# dcdc3to5.net
KiCad netlist of a schematic drawn in EAGLE
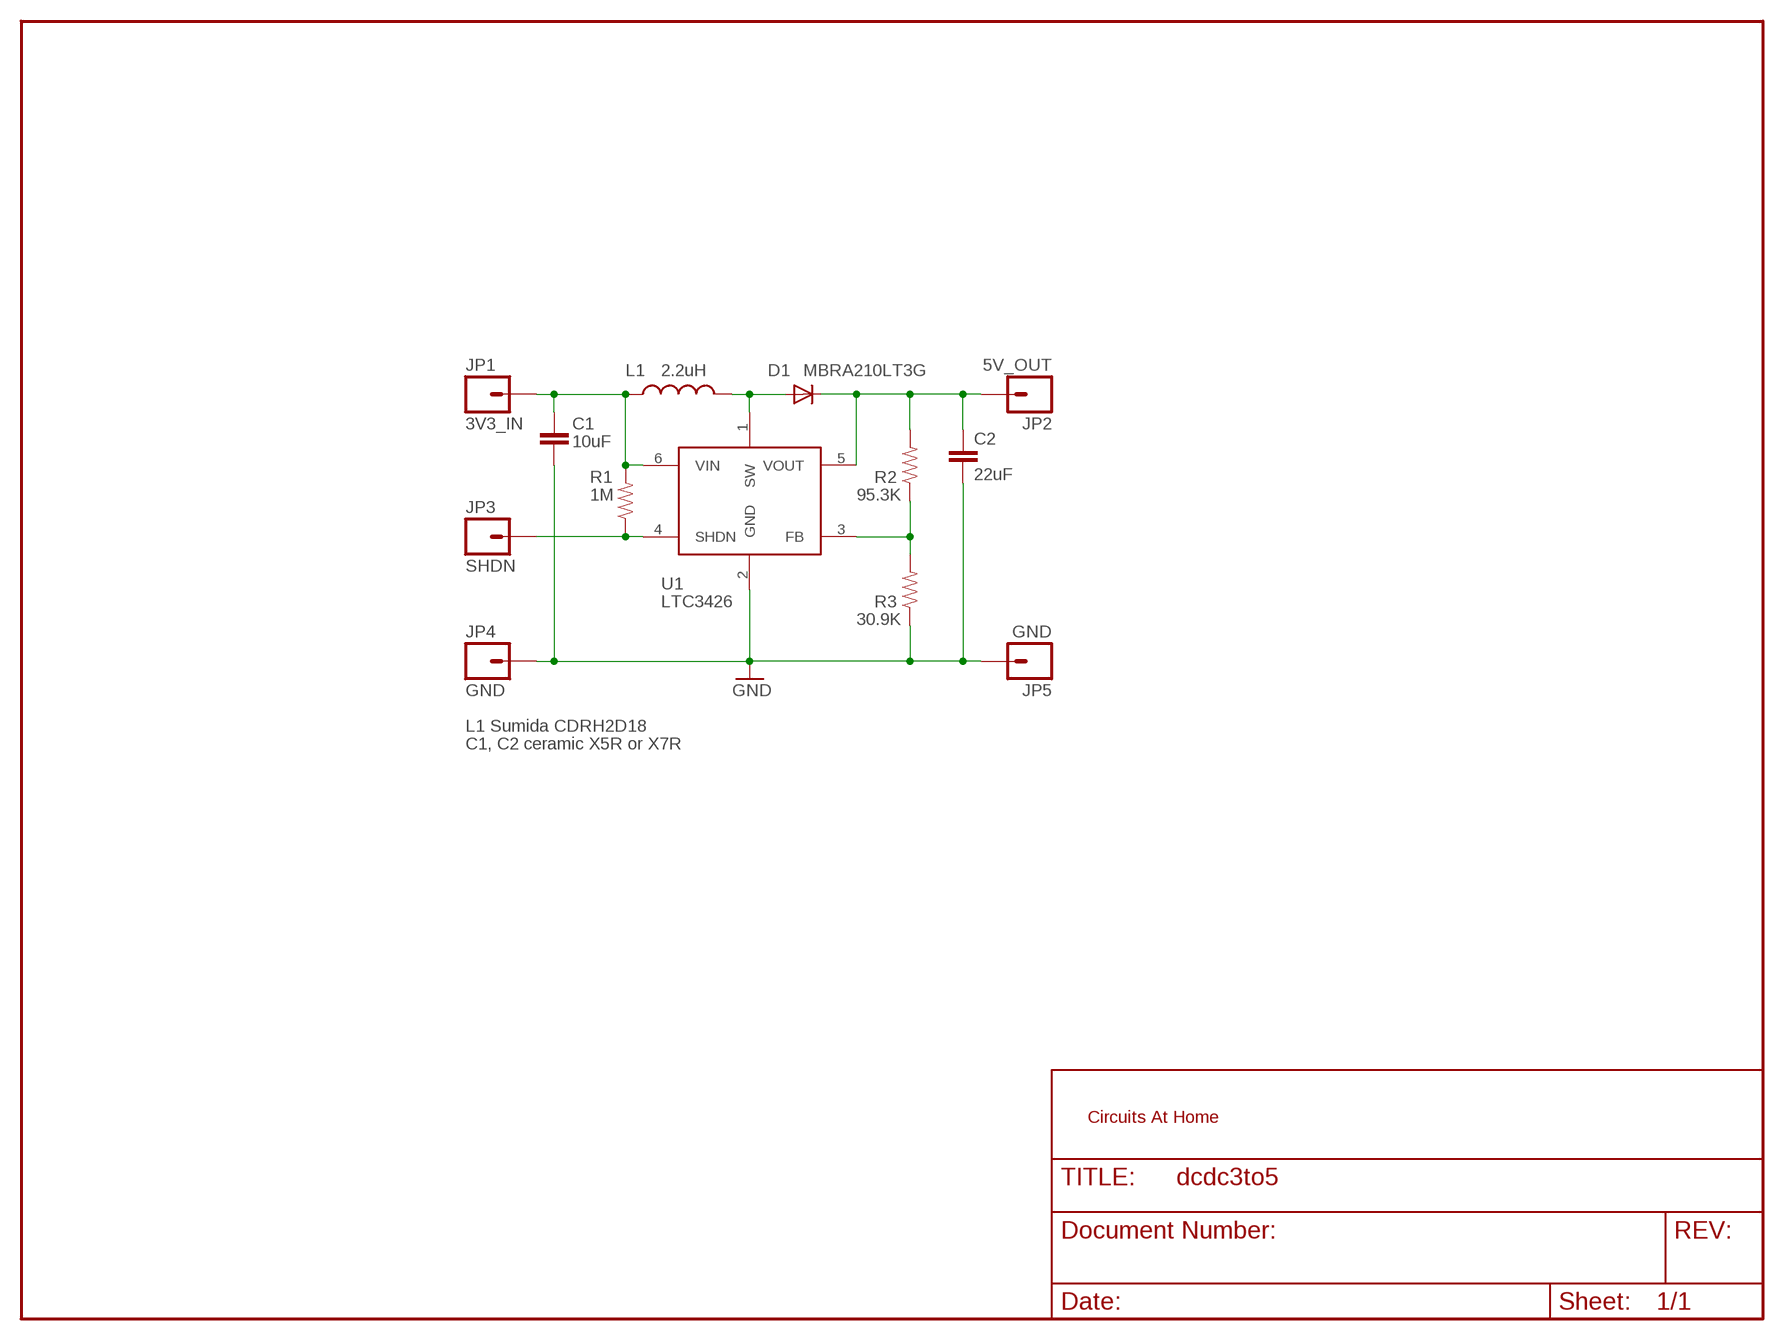
[diagram p0: schematic, sheet 1]

(export (version "E")
  (design (tool "Eeschema 10.0.6"))
  (components
    (comp (ref "C1")
      (value "10uF")
      (footprint "eagle-import:0603")
      (libsource (lib "eagle-import") (part "CAP0603"))
    )
    (comp (ref "C2")
      (value "22uF")
      (footprint "eagle-import:1206")
      (libsource (lib "eagle-import") (part "CAP1206"))
    )
    (comp (ref "D1")
      (value "MBRA210LT3G")
      (footprint "eagle-import:SMA-DIODE")
      (libsource (lib "eagle-import") (part "DIODESMA"))
    )
    (comp (ref "JP1")
      (value "3V3_IN")
      (footprint "eagle-import:1X01")
      (libsource (lib "eagle-import") (part "M01PTH"))
    )
    (comp (ref "JP2")
      (value "5V_OUT")
      (footprint "eagle-import:1X01")
      (libsource (lib "eagle-import") (part "M01PTH"))
    )
    (comp (ref "JP3")
      (value "SHDN")
      (footprint "eagle-import:1X01")
      (libsource (lib "eagle-import") (part "M01PTH"))
    )
    (comp (ref "JP4")
      (value "GND")
      (footprint "eagle-import:1X01")
      (libsource (lib "eagle-import") (part "M01PTH"))
    )
    (comp (ref "JP5")
      (value "GND")
      (footprint "eagle-import:1X01")
      (libsource (lib "eagle-import") (part "M01PTH"))
    )
    (comp (ref "L1")
      (value "2.2uH")
      (footprint "eagle-import:1_3X1_3")
      (libsource (lib "eagle-import") (part "INDUCTOR1313"))
    )
    (comp (ref "R1")
      (value "1M")
      (footprint "eagle-import:0603")
      (libsource (lib "eagle-import") (part "RESISTOR0603"))
    )
    (comp (ref "R2")
      (value "95.3K")
      (footprint "eagle-import:0603")
      (libsource (lib "eagle-import") (part "RESISTOR0603"))
    )
    (comp (ref "R3")
      (value "30.9K")
      (footprint "eagle-import:0603")
      (libsource (lib "eagle-import") (part "RESISTOR0603"))
    )
    (comp (ref "U1")
      (value "LTC3426")
      (footprint "eagle-import:SOT23-6")
      (libsource (lib "eagle-import") (part "LTC3426"))
    )
  )
  (nets
    (net (code "1") (name "GND") (class "Default")
      (node (ref "C1") (pin "2") (pinfunction "2_2") (pintype "passive"))
      (node (ref "C2") (pin "2") (pinfunction "2_2") (pintype "passive"))
      (node (ref "JP4") (pin "1") (pinfunction "1_1") (pintype "passive"))
      (node (ref "JP5") (pin "1") (pinfunction "1_1") (pintype "passive"))
      (node (ref "R3") (pin "1") (pinfunction "1_1") (pintype "passive"))
      (node (ref "U1") (pin "2") (pinfunction "GND_2") (pintype "passive"))
    )
    (net (code "2") (name "Net-(L1-1)") (class "Default")
      (node (ref "C1") (pin "1") (pinfunction "1_1") (pintype "passive"))
      (node (ref "JP1") (pin "1") (pinfunction "1_1") (pintype "passive"))
      (node (ref "L1") (pin "P$1") (pinfunction "1_P$1") (pintype "passive"))
      (node (ref "R1") (pin "2") (pinfunction "2_2") (pintype "passive"))
      (node (ref "U1") (pin "6") (pinfunction "VIN_6") (pintype "power_in"))
    )
    (net (code "3") (name "Net-(L1-2)") (class "Default")
      (node (ref "D1") (pin "A") (pinfunction "A_A") (pintype "passive"))
      (node (ref "L1") (pin "P$2") (pinfunction "2_P$2") (pintype "passive"))
      (node (ref "U1") (pin "1") (pinfunction "SW_1") (pintype "passive"))
    )
    (net (code "4") (name "Net-(U1-FB)") (class "Default")
      (node (ref "R2") (pin "1") (pinfunction "1_1") (pintype "passive"))
      (node (ref "R3") (pin "2") (pinfunction "2_2") (pintype "passive"))
      (node (ref "U1") (pin "3") (pinfunction "FB_3") (pintype "input"))
    )
    (net (code "5") (name "Net-(U1-SHDN)") (class "Default")
      (node (ref "JP3") (pin "1") (pinfunction "1_1") (pintype "passive"))
      (node (ref "R1") (pin "1") (pinfunction "1_1") (pintype "passive"))
      (node (ref "U1") (pin "4") (pinfunction "SHDN_4") (pintype "input"))
    )
    (net (code "6") (name "Net-(U1-VOUT)") (class "Default")
      (node (ref "C2") (pin "1") (pinfunction "1_1") (pintype "passive"))
      (node (ref "D1") (pin "C") (pinfunction "C_C") (pintype "passive"))
      (node (ref "JP2") (pin "1") (pinfunction "1_1") (pintype "passive"))
      (node (ref "R2") (pin "2") (pinfunction "2_2") (pintype "passive"))
      (node (ref "U1") (pin "5") (pinfunction "VOUT_5") (pintype "passive"))
    )
  )
)
